# or_gate_using_transister.net
KiCad netlist of a schematic drawn in EAGLE
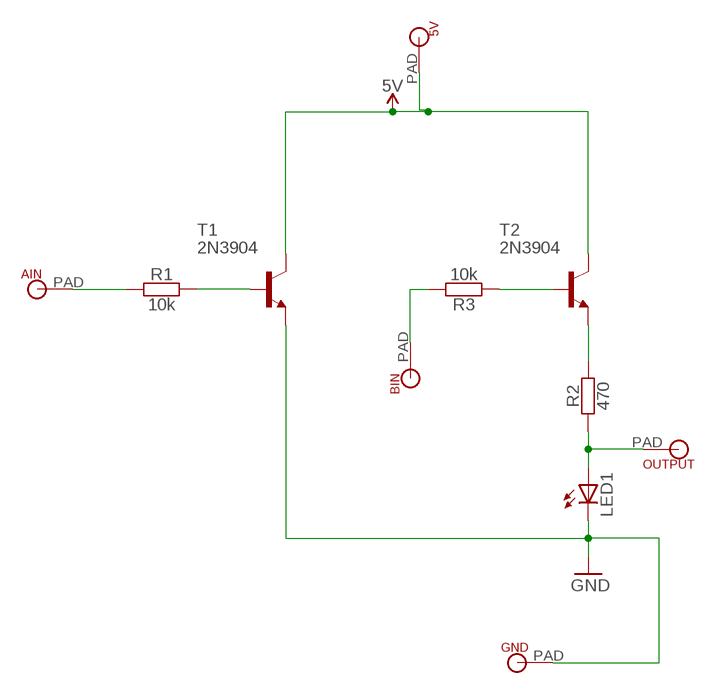
[diagram p0: schematic, sheet 1]

(export (version "E")
  (design (tool "Eeschema 10.0.6"))
  (components
    (comp (ref "5V")
      (value "MICROBIT_PAD")
      (footprint "eagle-import:MICROBIT_PAD")
      (libsource (lib "eagle-import") (part "MICROBIT_PAD"))
    )
    (comp (ref "AIN")
      (value "MICROBIT_PAD")
      (footprint "eagle-import:MICROBIT_PAD")
      (libsource (lib "eagle-import") (part "MICROBIT_PAD"))
    )
    (comp (ref "BIN")
      (value "MICROBIT_PAD")
      (footprint "eagle-import:MICROBIT_PAD")
      (libsource (lib "eagle-import") (part "MICROBIT_PAD"))
    )
    (comp (ref "GND")
      (value "MICROBIT_PAD")
      (footprint "eagle-import:MICROBIT_PAD")
      (libsource (lib "eagle-import") (part "MICROBIT_PAD"))
    )
    (comp (ref "LED1")
      (value "LED3MM")
      (footprint "eagle-import:LED3MM")
      (libsource (lib "eagle-import") (part "LED3MM"))
    )
    (comp (ref "OUTPUT")
      (value "MICROBIT_PAD")
      (footprint "eagle-import:MICROBIT_PAD")
      (libsource (lib "eagle-import") (part "MICROBIT_PAD"))
    )
    (comp (ref "R1")
      (value "10k")
      (footprint "eagle-import:R0207_7")
      (libsource (lib "eagle-import") (part "RESISTOR-07"))
    )
    (comp (ref "R2")
      (value "470")
      (footprint "eagle-import:R0207_7")
      (libsource (lib "eagle-import") (part "RESISTOR-07"))
    )
    (comp (ref "R3")
      (value "10k")
      (footprint "eagle-import:R0207_7")
      (libsource (lib "eagle-import") (part "RESISTOR-07"))
    )
    (comp (ref "T1")
      (value "2N3904")
      (footprint "eagle-import:TO92")
      (libsource (lib "eagle-import") (part "2N3904"))
    )
    (comp (ref "T2")
      (value "2N3904")
      (footprint "eagle-import:TO92")
      (libsource (lib "eagle-import") (part "2N3904"))
    )
  )
  (nets
    (net (code "1") (name "5V") (class "Default")
      (node (ref "5V") (pin "PAD") (pinfunction "P$1_PAD") (pintype "bidirectional"))
      (node (ref "T1") (pin "1") (pinfunction "C_1") (pintype "passive"))
      (node (ref "T2") (pin "1") (pinfunction "C_1") (pintype "passive"))
    )
    (net (code "2") (name "GND") (class "Default")
      (node (ref "GND") (pin "PAD") (pinfunction "P$1_PAD") (pintype "bidirectional"))
      (node (ref "LED1") (pin "K") (pinfunction "C_K") (pintype "passive"))
      (node (ref "T1") (pin "3") (pinfunction "E_3") (pintype "passive"))
    )
    (net (code "3") (name "Net-(AIN-P$1)") (class "Default")
      (node (ref "AIN") (pin "PAD") (pinfunction "P$1_PAD") (pintype "bidirectional"))
      (node (ref "R1") (pin "1") (pinfunction "1_1") (pintype "passive"))
    )
    (net (code "4") (name "Net-(BIN-P$1)") (class "Default")
      (node (ref "BIN") (pin "PAD") (pinfunction "P$1_PAD") (pintype "bidirectional"))
      (node (ref "R3") (pin "2") (pinfunction "2_2") (pintype "passive"))
    )
    (net (code "5") (name "Net-(OUTPUT-P$1)") (class "Default")
      (node (ref "LED1") (pin "A") (pinfunction "A_A") (pintype "passive"))
      (node (ref "OUTPUT") (pin "PAD") (pinfunction "P$1_PAD") (pintype "bidirectional"))
      (node (ref "R2") (pin "1") (pinfunction "1_1") (pintype "passive"))
    )
    (net (code "6") (name "Net-(T1-B)") (class "Default")
      (node (ref "R1") (pin "2") (pinfunction "2_2") (pintype "passive"))
      (node (ref "T1") (pin "2") (pinfunction "B_2") (pintype "passive"))
    )
    (net (code "7") (name "Net-(T2-B)") (class "Default")
      (node (ref "R3") (pin "1") (pinfunction "1_1") (pintype "passive"))
      (node (ref "T2") (pin "2") (pinfunction "B_2") (pintype "passive"))
    )
    (net (code "8") (name "Net-(T2-E)") (class "Default")
      (node (ref "R2") (pin "2") (pinfunction "2_2") (pintype "passive"))
      (node (ref "T2") (pin "3") (pinfunction "E_3") (pintype "passive"))
    )
  )
)
